# TopLevel.net
KiCad netlist of a schematic drawn in Altium Designer
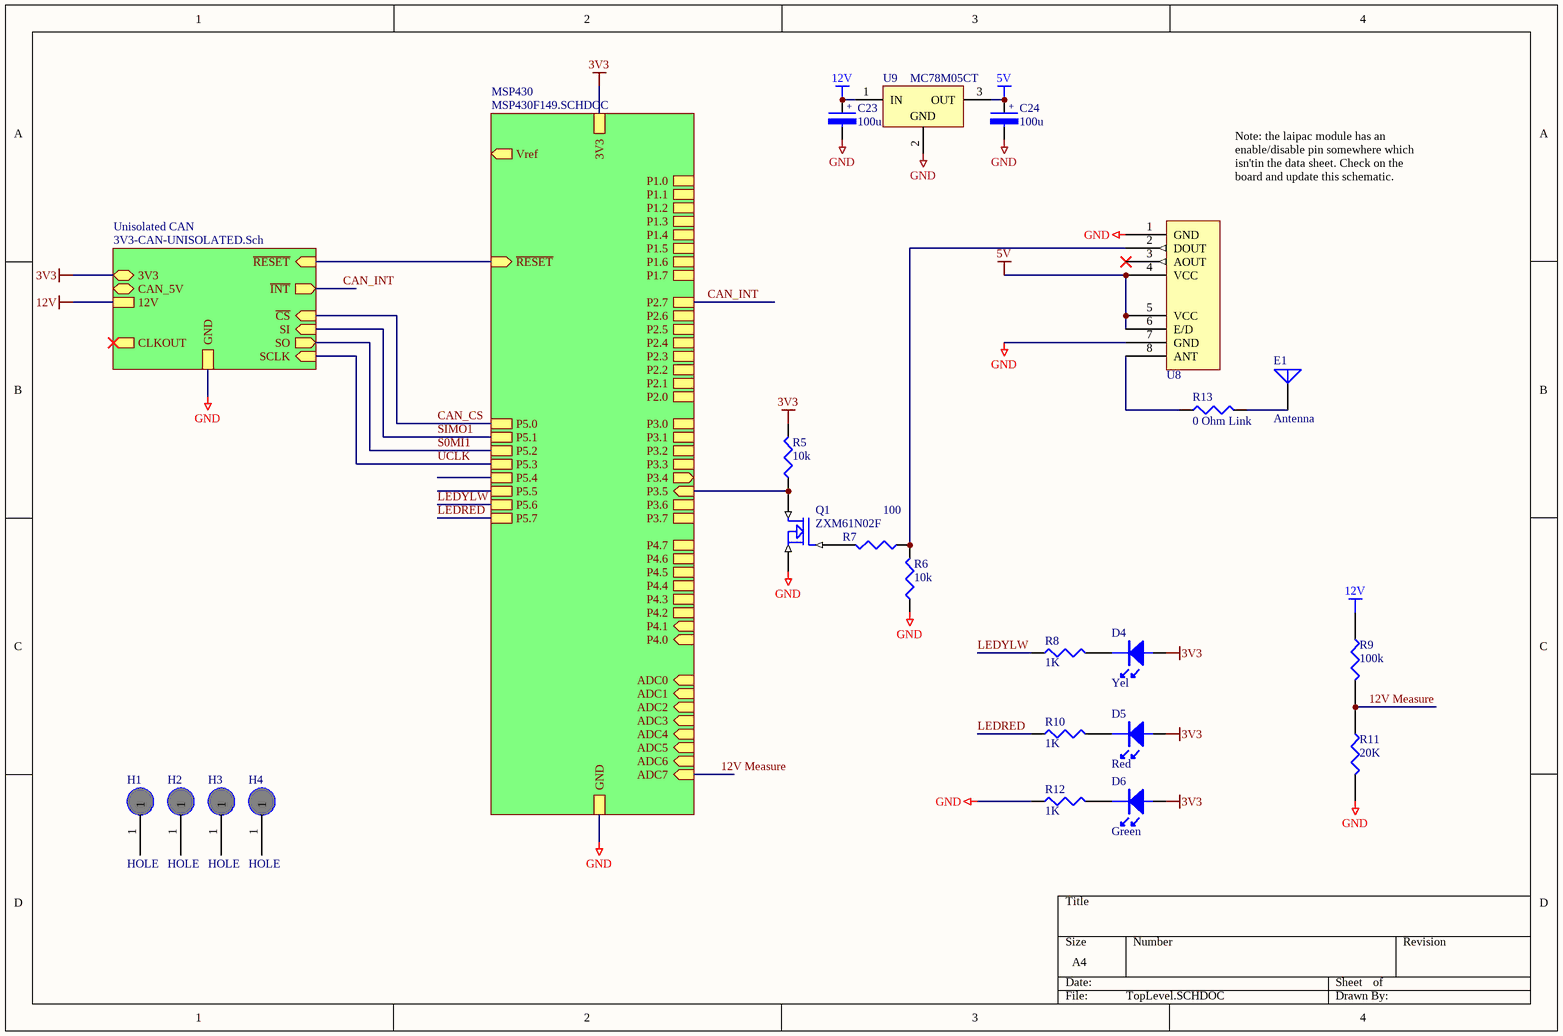
[diagram p0: TopLevel.SCHDOC]

(export (version "E")
  (design (tool "Eeschema 10.0.6"))
  (components
    (comp (ref "C23")
      (value "100u")
      (footprint "Footprint:1206")
      (description "Capacitor")
      (libsource (lib "RCLDQ") (part "CAP-POL"))
    )
    (comp (ref "C24")
      (value "100u")
      (footprint "Footprint:1206")
      (description "Capacitor")
      (libsource (lib "RCLDQ") (part "CAP-POL"))
    )
    (comp (ref "D4") (value "Yel") (footprint "Footprint:LED0.1") (libsource (lib "RCLDQ") (part "LED")))
    (comp (ref "D5") (value "Red") (footprint "Footprint:LED0.1") (libsource (lib "RCLDQ") (part "LED")))
    (comp (ref "D6") (value "Green") (footprint "Footprint:LED0.1") (libsource (lib "RCLDQ") (part "LED")))
    (comp (ref "E1")
      (value "Antenna")
      (footprint "PIN1")
      (description "Generic Antenna")
      (fields (field (name "PUBLISHER") "Altium Limited"))
      (libsource (lib "Miscellaneous Devices") (part "Antenna"))
    )
    (comp (ref "H1")
      (value "HOLE")
      (footprint "M2.5")
      (description "Hole")
      (libsource (lib "Miscellaneous") (part "HOLE"))
    )
    (comp (ref "H2")
      (value "HOLE")
      (footprint "M2.5")
      (description "Hole")
      (libsource (lib "Miscellaneous") (part "HOLE"))
    )
    (comp (ref "H3")
      (value "HOLE")
      (footprint "M2.5")
      (description "Hole")
      (libsource (lib "Miscellaneous") (part "HOLE"))
    )
    (comp (ref "H4")
      (value "HOLE")
      (footprint "M2.5")
      (description "Hole")
      (libsource (lib "Miscellaneous") (part "HOLE"))
    )
    (comp (ref "Q1")
      (value "ZXM61N02F")
      (footprint "SOT23-3")
      (description "1.7A, 20V N-Channel Enhancement mode FET")
      (libsource (lib "RCLDQ") (part "ZXM61N02F"))
    )
    (comp (ref "R5")
      (value "10k")
      (footprint "0603")
      (description "Resistor")
      (libsource (lib "RCLDQ") (part "RES1"))
    )
    (comp (ref "R6")
      (value "10k")
      (footprint "0603")
      (description "Resistor")
      (libsource (lib "RCLDQ") (part "RES1"))
    )
    (comp (ref "R7")
      (value "100")
      (footprint "0603")
      (description "Resistor")
      (libsource (lib "RCLDQ") (part "RES1"))
    )
    (comp (ref "R8")
      (value "1K")
      (footprint "0603")
      (description "Resistor")
      (libsource (lib "RCLDQ") (part "RES1"))
    )
    (comp (ref "R9") (value "100k") (footprint "1206") (libsource (lib "*") (part "RES1")))
    (comp (ref "R10")
      (value "1K")
      (footprint "0603")
      (description "Resistor")
      (libsource (lib "RCLDQ") (part "RES1"))
    )
    (comp (ref "R11") (value "20K") (footprint "1206") (libsource (lib "*") (part "RES1")))
    (comp (ref "R12")
      (value "1K")
      (footprint "0603")
      (description "Resistor")
      (libsource (lib "RCLDQ") (part "RES1"))
    )
    (comp (ref "R13")
      (value "0 Ohm Link")
      (footprint "0603")
      (description "Resistor")
      (libsource (lib "RCLDQ") (part "RES1"))
    )
    (comp (ref "U8") (value "RLPA") (libsource (lib "RF") (part "RLPA")))
    (comp (ref "U9")
      (value "MC78M05CT")
      (footprint "221A-04")
      (description "3-Terminal Medium-Current Positive Fixed Voltage Regulator")
      (fields (field (name "PUBLISHER") "Altium Limited"))
      (libsource (lib "Motorola Power Mgt Voltage Regulator") (part "MC78M05CT"))
    )
  )
  (nets
    (net (code "1") (name "/12V Measure") (class "Default")
      (node (ref "R11") (pin "1") (pinfunction "1_1") (pintype "passive"))
      (node (ref "R9") (pin "2") (pinfunction "2_2") (pintype "passive"))
    )
    (net (code "13") (name "/LEDRED") (class "Default")
      (node (ref "R10") (pin "1") (pinfunction "1_1") (pintype "passive"))
    )
    (net (code "14") (name "/LEDYLW") (class "Default")
      (node (ref "R8") (pin "1") (pinfunction "1_1") (pintype "passive"))
    )
    (net (code "35") (name "/P3.5") (class "Default")
      (node (ref "Q1") (pin "3") (pinfunction "D_3") (pintype "input"))
      (node (ref "R5") (pin "1") (pinfunction "1_1") (pintype "passive"))
    )
    (net (code "53") (name "3V3") (class "Default")
      (node (ref "D4") (pin "A") (pinfunction "A_A") (pintype "passive"))
      (node (ref "D5") (pin "A") (pinfunction "A_A") (pintype "passive"))
      (node (ref "D6") (pin "A") (pinfunction "A_A") (pintype "passive"))
      (node (ref "R5") (pin "2") (pinfunction "2_2") (pintype "passive"))
    )
    (net (code "54") (name "5V") (class "Default")
      (node (ref "C24") (pin "1") (pinfunction "1_1") (pintype "passive"))
      (node (ref "U8") (pin "4") (pinfunction "VCC_4") (pintype "power_in"))
      (node (ref "U8") (pin "5") (pinfunction "VCC_5") (pintype "power_in"))
      (node (ref "U8") (pin "6") (pinfunction "E/D_6") (pintype "power_in"))
      (node (ref "U9") (pin "3") (pinfunction "OUT_3") (pintype "power_in"))
    )
    (net (code "55") (name "12V") (class "Default")
      (node (ref "C23") (pin "1") (pinfunction "1_1") (pintype "passive"))
      (node (ref "R9") (pin "1") (pinfunction "1_1") (pintype "passive"))
      (node (ref "U9") (pin "1") (pinfunction "IN_1") (pintype "power_in"))
    )
    (net (code "56") (name "GND") (class "Default")
      (node (ref "C23") (pin "2") (pinfunction "2_2") (pintype "passive"))
      (node (ref "C24") (pin "2") (pinfunction "2_2") (pintype "passive"))
      (node (ref "Q1") (pin "2") (pinfunction "S_2") (pintype "input"))
      (node (ref "R11") (pin "2") (pinfunction "2_2") (pintype "passive"))
      (node (ref "R12") (pin "1") (pinfunction "1_1") (pintype "passive"))
      (node (ref "R6") (pin "1") (pinfunction "1_1") (pintype "passive"))
      (node (ref "U8") (pin "1") (pinfunction "GND_1") (pintype "power_in"))
      (node (ref "U8") (pin "7") (pinfunction "GND_7") (pintype "power_in"))
      (node (ref "U9") (pin "2") (pinfunction "GND_2") (pintype "power_in"))
    )
    (net (code "57") (name "Net-(D4-PadK)") (class "Default")
      (node (ref "D4") (pin "K") (pinfunction "K_K") (pintype "passive"))
      (node (ref "R8") (pin "2") (pinfunction "2_2") (pintype "passive"))
    )
    (net (code "58") (name "Net-(D5-PadK)") (class "Default")
      (node (ref "D5") (pin "K") (pinfunction "K_K") (pintype "passive"))
      (node (ref "R10") (pin "2") (pinfunction "2_2") (pintype "passive"))
    )
    (net (code "59") (name "Net-(D6-PadK)") (class "Default")
      (node (ref "D6") (pin "K") (pinfunction "K_K") (pintype "passive"))
      (node (ref "R12") (pin "2") (pinfunction "2_2") (pintype "passive"))
    )
    (net (code "60") (name "Net-(E1-A)") (class "Default")
      (node (ref "E1") (pin "1") (pinfunction "A_1") (pintype "passive"))
      (node (ref "R13") (pin "2") (pinfunction "2_2") (pintype "passive"))
    )
    (net (code "61") (name "Net-(Q1-G)") (class "Default")
      (node (ref "Q1") (pin "1") (pinfunction "G_1") (pintype "input"))
      (node (ref "R7") (pin "2") (pinfunction "2_2") (pintype "passive"))
    )
    (net (code "62") (name "Net-(U8-ANT)") (class "Default")
      (node (ref "R13") (pin "1") (pinfunction "1_1") (pintype "passive"))
      (node (ref "U8") (pin "8") (pinfunction "ANT_8") (pintype "power_in"))
    )
    (net (code "63") (name "Net-(U8-DOUT)") (class "Default")
      (node (ref "R6") (pin "2") (pinfunction "2_2") (pintype "passive"))
      (node (ref "R7") (pin "1") (pinfunction "1_1") (pintype "passive"))
      (node (ref "U8") (pin "2") (pinfunction "DOUT_2") (pintype "output"))
    )
    (net (code "64") (name "unconnected-(H1-Pad1)") (class "Default")
      (node (ref "H1") (pin "1") (pinfunction "1_1") (pintype "passive"))
    )
    (net (code "65") (name "unconnected-(H2-Pad1)") (class "Default")
      (node (ref "H2") (pin "1") (pinfunction "1_1") (pintype "passive"))
    )
    (net (code "66") (name "unconnected-(H3-Pad1)") (class "Default")
      (node (ref "H3") (pin "1") (pinfunction "1_1") (pintype "passive"))
    )
    (net (code "67") (name "unconnected-(H4-Pad1)") (class "Default")
      (node (ref "H4") (pin "1") (pinfunction "1_1") (pintype "passive"))
    )
    (net (code "68") (name "unconnected-(U8-AOUT-Pad3)") (class "Default")
      (node (ref "U8") (pin "3") (pinfunction "AOUT_3") (pintype "output+no_connect"))
    )
  )
)
